# ws2812b.net
KiCad netlist of a schematic drawn in Altium Designer
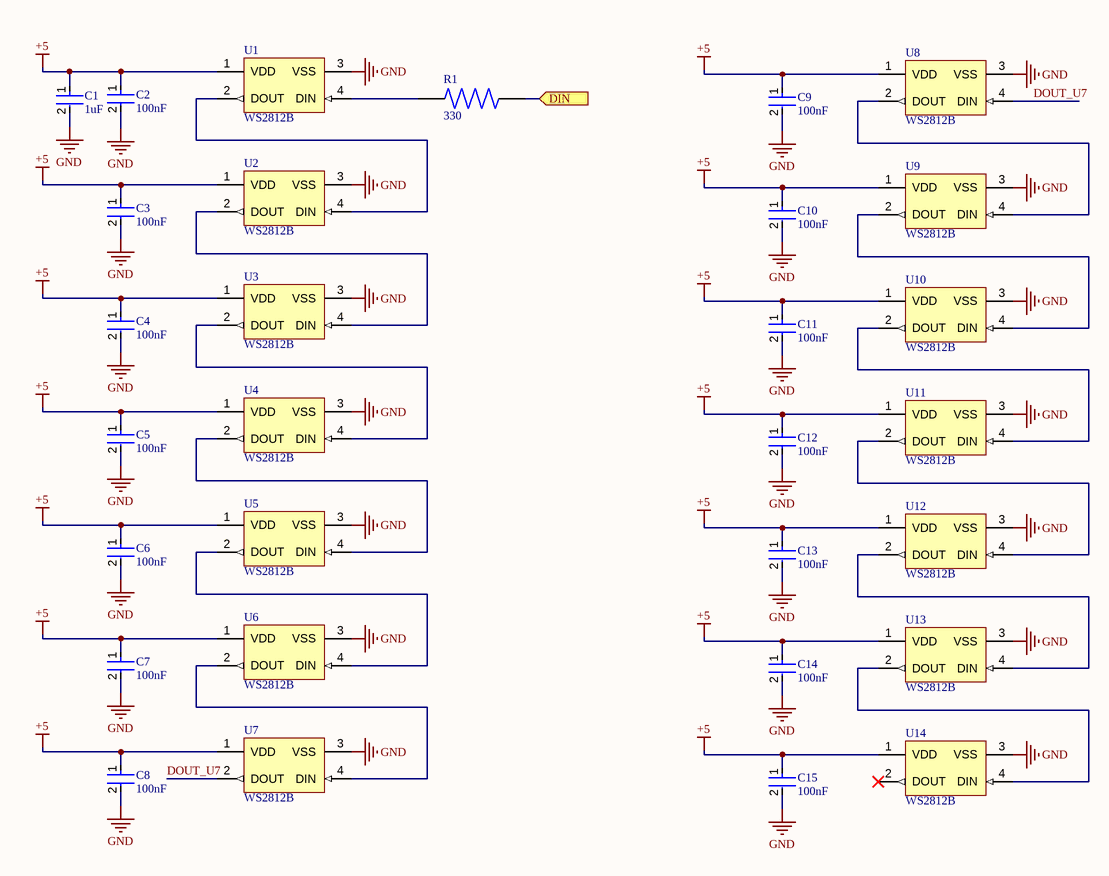
[diagram p0: ws2812b.SchDoc]

(export (version "E")
  (design (tool "Eeschema 10.0.6"))
  (components
    (comp (ref "C1")
      (value "1uF")
      (footprint "FP-CGA3E-0_3-0_1-IPC_A")
      (description "Cap Ceramic 1uF 16V X7R 10% Pad SMD 0603 +125°C Automotive T/R")
      (fields (field (name "TOLERANCE") "10%"))
      (libsource (lib "Altium Content Vault") (part "b4654b650e69147ec39a6b967a45e02"))
    )
    (comp (ref "C2")
      (value "100nF")
      (footprint "FP-CL10-IPC_A")
      (description "Cap Ceramic 100nF 16V X7R ±10% Pad SMD 0603 +125°C T/R")
      (fields (field (name "TOLERANCE") "10%"))
      (libsource (lib "Altium Content Vault") (part "b4654b650e69147ec39a6b967a45e02"))
    )
    (comp (ref "C3")
      (value "100nF")
      (footprint "FP-CL10-IPC_A")
      (description "Cap Ceramic 100nF 16V X7R ±10% Pad SMD 0603 +125°C T/R")
      (fields (field (name "TOLERANCE") "10%"))
      (libsource (lib "Altium Content Vault") (part "b4654b650e69147ec39a6b967a45e02"))
    )
    (comp (ref "C4")
      (value "100nF")
      (footprint "FP-CL10-IPC_A")
      (description "Cap Ceramic 100nF 16V X7R ±10% Pad SMD 0603 +125°C T/R")
      (fields (field (name "TOLERANCE") "10%"))
      (libsource (lib "Altium Content Vault") (part "b4654b650e69147ec39a6b967a45e02"))
    )
    (comp (ref "C5")
      (value "100nF")
      (footprint "FP-CL10-IPC_A")
      (description "Cap Ceramic 100nF 16V X7R ±10% Pad SMD 0603 +125°C T/R")
      (fields (field (name "TOLERANCE") "10%"))
      (libsource (lib "Altium Content Vault") (part "b4654b650e69147ec39a6b967a45e02"))
    )
    (comp (ref "C6")
      (value "100nF")
      (footprint "FP-CL10-IPC_A")
      (description "Cap Ceramic 100nF 16V X7R ±10% Pad SMD 0603 +125°C T/R")
      (fields (field (name "TOLERANCE") "10%"))
      (libsource (lib "Altium Content Vault") (part "b4654b650e69147ec39a6b967a45e02"))
    )
    (comp (ref "C7")
      (value "100nF")
      (footprint "FP-CL10-IPC_A")
      (description "Cap Ceramic 100nF 16V X7R ±10% Pad SMD 0603 +125°C T/R")
      (fields (field (name "TOLERANCE") "10%"))
      (libsource (lib "Altium Content Vault") (part "b4654b650e69147ec39a6b967a45e02"))
    )
    (comp (ref "C8")
      (value "100nF")
      (footprint "FP-CL10-IPC_A")
      (description "Cap Ceramic 100nF 16V X7R ±10% Pad SMD 0603 +125°C T/R")
      (fields (field (name "TOLERANCE") "10%"))
      (libsource (lib "Altium Content Vault") (part "b4654b650e69147ec39a6b967a45e02"))
    )
    (comp (ref "C9")
      (value "100nF")
      (footprint "FP-CL10-IPC_A")
      (description "Cap Ceramic 100nF 16V X7R ±10% Pad SMD 0603 +125°C T/R")
      (fields (field (name "TOLERANCE") "10%"))
      (libsource (lib "Altium Content Vault") (part "b4654b650e69147ec39a6b967a45e02"))
    )
    (comp (ref "C10")
      (value "100nF")
      (footprint "FP-CL10-IPC_A")
      (description "Cap Ceramic 100nF 16V X7R ±10% Pad SMD 0603 +125°C T/R")
      (fields (field (name "TOLERANCE") "10%"))
      (libsource (lib "Altium Content Vault") (part "b4654b650e69147ec39a6b967a45e02"))
    )
    (comp (ref "C11")
      (value "100nF")
      (footprint "FP-CL10-IPC_A")
      (description "Cap Ceramic 100nF 16V X7R ±10% Pad SMD 0603 +125°C T/R")
      (fields (field (name "TOLERANCE") "10%"))
      (libsource (lib "Altium Content Vault") (part "b4654b650e69147ec39a6b967a45e02"))
    )
    (comp (ref "C12")
      (value "100nF")
      (footprint "FP-CL10-IPC_A")
      (description "Cap Ceramic 100nF 16V X7R ±10% Pad SMD 0603 +125°C T/R")
      (fields (field (name "TOLERANCE") "10%"))
      (libsource (lib "Altium Content Vault") (part "b4654b650e69147ec39a6b967a45e02"))
    )
    (comp (ref "C13")
      (value "100nF")
      (footprint "FP-CL10-IPC_A")
      (description "Cap Ceramic 100nF 16V X7R ±10% Pad SMD 0603 +125°C T/R")
      (fields (field (name "TOLERANCE") "10%"))
      (libsource (lib "Altium Content Vault") (part "b4654b650e69147ec39a6b967a45e02"))
    )
    (comp (ref "C14")
      (value "100nF")
      (footprint "FP-CL10-IPC_A")
      (description "Cap Ceramic 100nF 16V X7R ±10% Pad SMD 0603 +125°C T/R")
      (fields (field (name "TOLERANCE") "10%"))
      (libsource (lib "Altium Content Vault") (part "b4654b650e69147ec39a6b967a45e02"))
    )
    (comp (ref "C15")
      (value "100nF")
      (footprint "FP-CL10-IPC_A")
      (description "Cap Ceramic 100nF 16V X7R ±10% Pad SMD 0603 +125°C T/R")
      (fields (field (name "TOLERANCE") "10%"))
      (libsource (lib "Altium Content Vault") (part "b4654b650e69147ec39a6b967a45e02"))
    )
    (comp (ref "R1")
      (value "330")
      (footprint "RES_ERJ-PB3B3300V")
      (fields (field (name "MP") "ERJ-PB3B3300V") (field (name "MF") "Panasonic"))
      (libsource (lib "Lin Fu") (part "ERJ-PB3B3300V"))
    )
    (comp (ref "U1")
      (value "WS2812B")
      (footprint "ADAI-WS2812B_V")
      (fields (field (name "MANUFACTURER") "Adafruit Industries"))
      (libsource (lib "Lin Fu") (part "ADAI-WS2812B-4"))
    )
    (comp (ref "U2")
      (value "WS2812B")
      (footprint "ADAI-WS2812B_V")
      (fields (field (name "MANUFACTURER") "Adafruit Industries"))
      (libsource (lib "Lin Fu") (part "ADAI-WS2812B-4"))
    )
    (comp (ref "U3")
      (value "WS2812B")
      (footprint "ADAI-WS2812B_V")
      (fields (field (name "MANUFACTURER") "Adafruit Industries"))
      (libsource (lib "Lin Fu") (part "ADAI-WS2812B-4"))
    )
    (comp (ref "U4")
      (value "WS2812B")
      (footprint "ADAI-WS2812B_V")
      (fields (field (name "MANUFACTURER") "Adafruit Industries"))
      (libsource (lib "Lin Fu") (part "ADAI-WS2812B-4"))
    )
    (comp (ref "U5")
      (value "WS2812B")
      (footprint "ADAI-WS2812B_V")
      (fields (field (name "MANUFACTURER") "Adafruit Industries"))
      (libsource (lib "Lin Fu") (part "ADAI-WS2812B-4"))
    )
    (comp (ref "U6")
      (value "WS2812B")
      (footprint "ADAI-WS2812B_V")
      (fields (field (name "MANUFACTURER") "Adafruit Industries"))
      (libsource (lib "Lin Fu") (part "ADAI-WS2812B-4"))
    )
    (comp (ref "U7")
      (value "WS2812B")
      (footprint "ADAI-WS2812B_V")
      (fields (field (name "MANUFACTURER") "Adafruit Industries"))
      (libsource (lib "Lin Fu") (part "ADAI-WS2812B-4"))
    )
    (comp (ref "U8")
      (value "WS2812B")
      (footprint "ADAI-WS2812B_V")
      (fields (field (name "MANUFACTURER") "Adafruit Industries"))
      (libsource (lib "Lin Fu") (part "ADAI-WS2812B-4"))
    )
    (comp (ref "U9")
      (value "WS2812B")
      (footprint "ADAI-WS2812B_V")
      (fields (field (name "MANUFACTURER") "Adafruit Industries"))
      (libsource (lib "Lin Fu") (part "ADAI-WS2812B-4"))
    )
    (comp (ref "U10")
      (value "WS2812B")
      (footprint "ADAI-WS2812B_V")
      (fields (field (name "MANUFACTURER") "Adafruit Industries"))
      (libsource (lib "Lin Fu") (part "ADAI-WS2812B-4"))
    )
    (comp (ref "U11")
      (value "WS2812B")
      (footprint "ADAI-WS2812B_V")
      (fields (field (name "MANUFACTURER") "Adafruit Industries"))
      (libsource (lib "Lin Fu") (part "ADAI-WS2812B-4"))
    )
    (comp (ref "U12")
      (value "WS2812B")
      (footprint "ADAI-WS2812B_V")
      (fields (field (name "MANUFACTURER") "Adafruit Industries"))
      (libsource (lib "Lin Fu") (part "ADAI-WS2812B-4"))
    )
    (comp (ref "U13")
      (value "WS2812B")
      (footprint "ADAI-WS2812B_V")
      (fields (field (name "MANUFACTURER") "Adafruit Industries"))
      (libsource (lib "Lin Fu") (part "ADAI-WS2812B-4"))
    )
    (comp (ref "U14")
      (value "WS2812B")
      (footprint "ADAI-WS2812B_V")
      (fields (field (name "MANUFACTURER") "Adafruit Industries"))
      (libsource (lib "Lin Fu") (part "ADAI-WS2812B-4"))
    )
  )
  (nets
    (net (code "1") (name "+5") (class "Default")
      (node (ref "C1") (pin "1") (pinfunction "1_1") (pintype "passive"))
      (node (ref "C10") (pin "1") (pinfunction "1_1") (pintype "passive"))
      (node (ref "C11") (pin "1") (pinfunction "1_1") (pintype "passive"))
      (node (ref "C12") (pin "1") (pinfunction "1_1") (pintype "passive"))
      (node (ref "C13") (pin "1") (pinfunction "1_1") (pintype "passive"))
      (node (ref "C14") (pin "1") (pinfunction "1_1") (pintype "passive"))
      (node (ref "C15") (pin "1") (pinfunction "1_1") (pintype "passive"))
      (node (ref "C2") (pin "1") (pinfunction "1_1") (pintype "passive"))
      (node (ref "C3") (pin "1") (pinfunction "1_1") (pintype "passive"))
      (node (ref "C4") (pin "1") (pinfunction "1_1") (pintype "passive"))
      (node (ref "C5") (pin "1") (pinfunction "1_1") (pintype "passive"))
      (node (ref "C6") (pin "1") (pinfunction "1_1") (pintype "passive"))
      (node (ref "C7") (pin "1") (pinfunction "1_1") (pintype "passive"))
      (node (ref "C8") (pin "1") (pinfunction "1_1") (pintype "passive"))
      (node (ref "C9") (pin "1") (pinfunction "1_1") (pintype "passive"))
      (node (ref "U1") (pin "1") (pinfunction "VDD_1") (pintype "power_in"))
      (node (ref "U10") (pin "1") (pinfunction "VDD_1") (pintype "power_in"))
      (node (ref "U11") (pin "1") (pinfunction "VDD_1") (pintype "power_in"))
      (node (ref "U12") (pin "1") (pinfunction "VDD_1") (pintype "power_in"))
      (node (ref "U13") (pin "1") (pinfunction "VDD_1") (pintype "power_in"))
      (node (ref "U14") (pin "1") (pinfunction "VDD_1") (pintype "power_in"))
      (node (ref "U2") (pin "1") (pinfunction "VDD_1") (pintype "power_in"))
      (node (ref "U3") (pin "1") (pinfunction "VDD_1") (pintype "power_in"))
      (node (ref "U4") (pin "1") (pinfunction "VDD_1") (pintype "power_in"))
      (node (ref "U5") (pin "1") (pinfunction "VDD_1") (pintype "power_in"))
      (node (ref "U6") (pin "1") (pinfunction "VDD_1") (pintype "power_in"))
      (node (ref "U7") (pin "1") (pinfunction "VDD_1") (pintype "power_in"))
      (node (ref "U8") (pin "1") (pinfunction "VDD_1") (pintype "power_in"))
      (node (ref "U9") (pin "1") (pinfunction "VDD_1") (pintype "power_in"))
    )
    (net (code "2") (name "/DIN") (class "Default")
      (node (ref "R1") (pin "2") (pinfunction "2_2") (pintype "passive"))
    )
    (net (code "3") (name "/DOUT_U7") (class "Default")
      (node (ref "U7") (pin "2") (pinfunction "DOUT_2") (pintype "output"))
      (node (ref "U8") (pin "4") (pinfunction "DIN_4") (pintype "input"))
    )
    (net (code "4") (name "GND") (class "Default")
      (node (ref "C1") (pin "2") (pinfunction "2_2") (pintype "passive"))
      (node (ref "C10") (pin "2") (pinfunction "2_2") (pintype "passive"))
      (node (ref "C11") (pin "2") (pinfunction "2_2") (pintype "passive"))
      (node (ref "C12") (pin "2") (pinfunction "2_2") (pintype "passive"))
      (node (ref "C13") (pin "2") (pinfunction "2_2") (pintype "passive"))
      (node (ref "C14") (pin "2") (pinfunction "2_2") (pintype "passive"))
      (node (ref "C15") (pin "2") (pinfunction "2_2") (pintype "passive"))
      (node (ref "C2") (pin "2") (pinfunction "2_2") (pintype "passive"))
      (node (ref "C3") (pin "2") (pinfunction "2_2") (pintype "passive"))
      (node (ref "C4") (pin "2") (pinfunction "2_2") (pintype "passive"))
      (node (ref "C5") (pin "2") (pinfunction "2_2") (pintype "passive"))
      (node (ref "C6") (pin "2") (pinfunction "2_2") (pintype "passive"))
      (node (ref "C7") (pin "2") (pinfunction "2_2") (pintype "passive"))
      (node (ref "C8") (pin "2") (pinfunction "2_2") (pintype "passive"))
      (node (ref "C9") (pin "2") (pinfunction "2_2") (pintype "passive"))
      (node (ref "U1") (pin "3") (pinfunction "VSS_3") (pintype "power_in"))
      (node (ref "U10") (pin "3") (pinfunction "VSS_3") (pintype "power_in"))
      (node (ref "U11") (pin "3") (pinfunction "VSS_3") (pintype "power_in"))
      (node (ref "U12") (pin "3") (pinfunction "VSS_3") (pintype "power_in"))
      (node (ref "U13") (pin "3") (pinfunction "VSS_3") (pintype "power_in"))
      (node (ref "U14") (pin "3") (pinfunction "VSS_3") (pintype "power_in"))
      (node (ref "U2") (pin "3") (pinfunction "VSS_3") (pintype "power_in"))
      (node (ref "U3") (pin "3") (pinfunction "VSS_3") (pintype "power_in"))
      (node (ref "U4") (pin "3") (pinfunction "VSS_3") (pintype "power_in"))
      (node (ref "U5") (pin "3") (pinfunction "VSS_3") (pintype "power_in"))
      (node (ref "U6") (pin "3") (pinfunction "VSS_3") (pintype "power_in"))
      (node (ref "U7") (pin "3") (pinfunction "VSS_3") (pintype "power_in"))
      (node (ref "U8") (pin "3") (pinfunction "VSS_3") (pintype "power_in"))
      (node (ref "U9") (pin "3") (pinfunction "VSS_3") (pintype "power_in"))
    )
    (net (code "5") (name "Net-(U1-DIN)") (class "Default")
      (node (ref "R1") (pin "1") (pinfunction "1_1") (pintype "passive"))
      (node (ref "U1") (pin "4") (pinfunction "DIN_4") (pintype "input"))
    )
    (net (code "6") (name "Net-(U1-DOUT)") (class "Default")
      (node (ref "U1") (pin "2") (pinfunction "DOUT_2") (pintype "output"))
      (node (ref "U2") (pin "4") (pinfunction "DIN_4") (pintype "input"))
    )
    (net (code "7") (name "Net-(U2-DOUT)") (class "Default")
      (node (ref "U2") (pin "2") (pinfunction "DOUT_2") (pintype "output"))
      (node (ref "U3") (pin "4") (pinfunction "DIN_4") (pintype "input"))
    )
    (net (code "8") (name "Net-(U3-DOUT)") (class "Default")
      (node (ref "U3") (pin "2") (pinfunction "DOUT_2") (pintype "output"))
      (node (ref "U4") (pin "4") (pinfunction "DIN_4") (pintype "input"))
    )
    (net (code "9") (name "Net-(U4-DOUT)") (class "Default")
      (node (ref "U4") (pin "2") (pinfunction "DOUT_2") (pintype "output"))
      (node (ref "U5") (pin "4") (pinfunction "DIN_4") (pintype "input"))
    )
    (net (code "10") (name "Net-(U5-DOUT)") (class "Default")
      (node (ref "U5") (pin "2") (pinfunction "DOUT_2") (pintype "output"))
      (node (ref "U6") (pin "4") (pinfunction "DIN_4") (pintype "input"))
    )
    (net (code "11") (name "Net-(U6-DOUT)") (class "Default")
      (node (ref "U6") (pin "2") (pinfunction "DOUT_2") (pintype "output"))
      (node (ref "U7") (pin "4") (pinfunction "DIN_4") (pintype "input"))
    )
    (net (code "12") (name "Net-(U8-DOUT)") (class "Default")
      (node (ref "U8") (pin "2") (pinfunction "DOUT_2") (pintype "output"))
      (node (ref "U9") (pin "4") (pinfunction "DIN_4") (pintype "input"))
    )
    (net (code "13") (name "Net-(U10-DIN)") (class "Default")
      (node (ref "U10") (pin "4") (pinfunction "DIN_4") (pintype "input"))
      (node (ref "U9") (pin "2") (pinfunction "DOUT_2") (pintype "output"))
    )
    (net (code "14") (name "Net-(U10-DOUT)") (class "Default")
      (node (ref "U10") (pin "2") (pinfunction "DOUT_2") (pintype "output"))
      (node (ref "U11") (pin "4") (pinfunction "DIN_4") (pintype "input"))
    )
    (net (code "15") (name "Net-(U11-DOUT)") (class "Default")
      (node (ref "U11") (pin "2") (pinfunction "DOUT_2") (pintype "output"))
      (node (ref "U12") (pin "4") (pinfunction "DIN_4") (pintype "input"))
    )
    (net (code "16") (name "Net-(U12-DOUT)") (class "Default")
      (node (ref "U12") (pin "2") (pinfunction "DOUT_2") (pintype "output"))
      (node (ref "U13") (pin "4") (pinfunction "DIN_4") (pintype "input"))
    )
    (net (code "17") (name "Net-(U13-DOUT)") (class "Default")
      (node (ref "U13") (pin "2") (pinfunction "DOUT_2") (pintype "output"))
      (node (ref "U14") (pin "4") (pinfunction "DIN_4") (pintype "input"))
    )
    (net (code "18") (name "unconnected-(U14-DOUT-Pad2)") (class "Default")
      (node (ref "U14") (pin "2") (pinfunction "DOUT_2") (pintype "output+no_connect"))
    )
  )
)
